# mcp23016-8buton8led_hw2_0.net
KiCad netlist of a schematic drawn in EAGLE
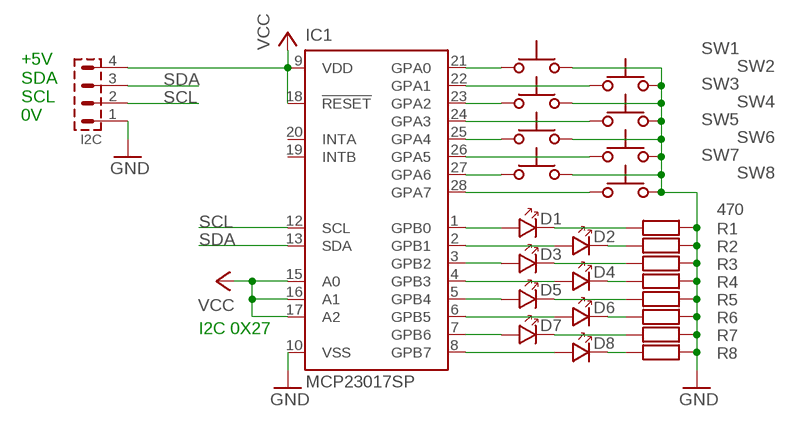
[diagram p0: schematic, sheet 1]

(export (version "E")
  (design (tool "Eeschema 10.0.6"))
  (components
    (comp (ref "D1")
      (value "LED_5")
      (footprint "eagle-import:LED_5")
      (libsource (lib "eagle-import") (part "LED_5"))
    )
    (comp (ref "D2")
      (value "LED_5")
      (footprint "eagle-import:LED_5")
      (libsource (lib "eagle-import") (part "LED_5"))
    )
    (comp (ref "D3")
      (value "LED_5")
      (footprint "eagle-import:LED_5")
      (libsource (lib "eagle-import") (part "LED_5"))
    )
    (comp (ref "D4")
      (value "LED_5")
      (footprint "eagle-import:LED_5")
      (libsource (lib "eagle-import") (part "LED_5"))
    )
    (comp (ref "D5")
      (value "LED_5")
      (footprint "eagle-import:LED_5")
      (libsource (lib "eagle-import") (part "LED_5"))
    )
    (comp (ref "D6")
      (value "LED_5")
      (footprint "eagle-import:LED_5")
      (libsource (lib "eagle-import") (part "LED_5"))
    )
    (comp (ref "D7")
      (value "LED_5")
      (footprint "eagle-import:LED_5")
      (libsource (lib "eagle-import") (part "LED_5"))
    )
    (comp (ref "D8")
      (value "LED_5")
      (footprint "eagle-import:LED_5")
      (libsource (lib "eagle-import") (part "LED_5"))
    )
    (comp (ref "I2C")
      (value "S1G4_JUMP")
      (footprint "eagle-import:S1G4_JUM")
      (libsource (lib "eagle-import") (part "S1G4_JUMP"))
    )
    (comp (ref "IC1")
      (value "MCP23017SP")
      (footprint "eagle-import:DIL28-3")
      (fields (field (name "MF") "MICROCHIP") (field (name "MPN") "MCP23017-E/SP"))
      (libsource (lib "eagle-import") (part "MCP23017SP"))
    )
    (comp (ref "R1")
      (value "470")
      (footprint "eagle-import:R-5")
      (libsource (lib "eagle-import") (part "R_5"))
    )
    (comp (ref "R2")
      (value "R_5")
      (footprint "eagle-import:R-5")
      (libsource (lib "eagle-import") (part "R_5"))
    )
    (comp (ref "R3")
      (value "R_5")
      (footprint "eagle-import:R-5")
      (libsource (lib "eagle-import") (part "R_5"))
    )
    (comp (ref "R4")
      (value "R_5")
      (footprint "eagle-import:R-5")
      (libsource (lib "eagle-import") (part "R_5"))
    )
    (comp (ref "R5")
      (value "R_5")
      (footprint "eagle-import:R-5")
      (libsource (lib "eagle-import") (part "R_5"))
    )
    (comp (ref "R6")
      (value "R_5")
      (footprint "eagle-import:R-5")
      (libsource (lib "eagle-import") (part "R_5"))
    )
    (comp (ref "R7")
      (value "R_5")
      (footprint "eagle-import:R-5")
      (libsource (lib "eagle-import") (part "R_5"))
    )
    (comp (ref "R8")
      (value "R_5")
      (footprint "eagle-import:R-5")
      (libsource (lib "eagle-import") (part "R_5"))
    )
    (comp (ref "SW1")
      (value "P-B1720")
      (footprint "eagle-import:P-B1720")
      (libsource (lib "eagle-import") (part "P-B1720"))
    )
    (comp (ref "SW2")
      (value "P-B1720")
      (footprint "eagle-import:P-B1720")
      (libsource (lib "eagle-import") (part "P-B1720"))
    )
    (comp (ref "SW3")
      (value "P-B1720")
      (footprint "eagle-import:P-B1720")
      (libsource (lib "eagle-import") (part "P-B1720"))
    )
    (comp (ref "SW4")
      (value "P-B1720")
      (footprint "eagle-import:P-B1720")
      (libsource (lib "eagle-import") (part "P-B1720"))
    )
    (comp (ref "SW5")
      (value "P-B1720")
      (footprint "eagle-import:P-B1720")
      (libsource (lib "eagle-import") (part "P-B1720"))
    )
    (comp (ref "SW6")
      (value "P-B1720")
      (footprint "eagle-import:P-B1720")
      (libsource (lib "eagle-import") (part "P-B1720"))
    )
    (comp (ref "SW7")
      (value "P-B1720")
      (footprint "eagle-import:P-B1720")
      (libsource (lib "eagle-import") (part "P-B1720"))
    )
    (comp (ref "SW8")
      (value "P-B1720")
      (footprint "eagle-import:P-B1720")
      (libsource (lib "eagle-import") (part "P-B1720"))
    )
  )
  (nets
    (net (code "1") (name "/SCL") (class "Default")
      (node (ref "I2C") (pin "2") (pinfunction "2_2") (pintype "passive"))
      (node (ref "IC1") (pin "12") (pinfunction "SCL_12") (pintype "input"))
    )
    (net (code "2") (name "/SDA") (class "Default")
      (node (ref "I2C") (pin "3") (pinfunction "3_3") (pintype "passive"))
      (node (ref "IC1") (pin "13") (pinfunction "SDA_13") (pintype "bidirectional"))
    )
    (net (code "3") (name "GND") (class "Default")
      (node (ref "I2C") (pin "1") (pinfunction "1_1") (pintype "passive"))
      (node (ref "IC1") (pin "10") (pinfunction "VSS_10") (pintype "power_in"))
      (node (ref "R1") (pin "2") (pinfunction "2_2") (pintype "passive"))
      (node (ref "R2") (pin "2") (pinfunction "2_2") (pintype "passive"))
      (node (ref "R3") (pin "2") (pinfunction "2_2") (pintype "passive"))
      (node (ref "R4") (pin "2") (pinfunction "2_2") (pintype "passive"))
      (node (ref "R5") (pin "2") (pinfunction "2_2") (pintype "passive"))
      (node (ref "R6") (pin "2") (pinfunction "2_2") (pintype "passive"))
      (node (ref "R7") (pin "2") (pinfunction "2_2") (pintype "passive"))
      (node (ref "R8") (pin "2") (pinfunction "2_2") (pintype "passive"))
      (node (ref "SW1") (pin "2") (pinfunction "2_2") (pintype "passive"))
      (node (ref "SW2") (pin "2") (pinfunction "2_2") (pintype "passive"))
      (node (ref "SW3") (pin "2") (pinfunction "2_2") (pintype "passive"))
      (node (ref "SW4") (pin "2") (pinfunction "2_2") (pintype "passive"))
      (node (ref "SW5") (pin "2") (pinfunction "2_2") (pintype "passive"))
      (node (ref "SW6") (pin "2") (pinfunction "2_2") (pintype "passive"))
      (node (ref "SW7") (pin "2") (pinfunction "2_2") (pintype "passive"))
      (node (ref "SW8") (pin "2") (pinfunction "2_2") (pintype "passive"))
    )
    (net (code "4") (name "Net-(D1-PadK)") (class "Default")
      (node (ref "D1") (pin "K") (pinfunction "K_K") (pintype "passive"))
      (node (ref "R1") (pin "1") (pinfunction "1_1") (pintype "passive"))
    )
    (net (code "5") (name "Net-(D2-PadK)") (class "Default")
      (node (ref "D2") (pin "K") (pinfunction "K_K") (pintype "passive"))
      (node (ref "R2") (pin "1") (pinfunction "1_1") (pintype "passive"))
    )
    (net (code "6") (name "Net-(D3-PadK)") (class "Default")
      (node (ref "D3") (pin "K") (pinfunction "K_K") (pintype "passive"))
      (node (ref "R3") (pin "1") (pinfunction "1_1") (pintype "passive"))
    )
    (net (code "7") (name "Net-(D4-PadK)") (class "Default")
      (node (ref "D4") (pin "K") (pinfunction "K_K") (pintype "passive"))
      (node (ref "R4") (pin "1") (pinfunction "1_1") (pintype "passive"))
    )
    (net (code "8") (name "Net-(D5-PadK)") (class "Default")
      (node (ref "D5") (pin "K") (pinfunction "K_K") (pintype "passive"))
      (node (ref "R5") (pin "1") (pinfunction "1_1") (pintype "passive"))
    )
    (net (code "9") (name "Net-(D6-PadK)") (class "Default")
      (node (ref "D6") (pin "K") (pinfunction "K_K") (pintype "passive"))
      (node (ref "R6") (pin "1") (pinfunction "1_1") (pintype "passive"))
    )
    (net (code "10") (name "Net-(D7-PadK)") (class "Default")
      (node (ref "D7") (pin "K") (pinfunction "K_K") (pintype "passive"))
      (node (ref "R7") (pin "1") (pinfunction "1_1") (pintype "passive"))
    )
    (net (code "11") (name "Net-(D8-PadK)") (class "Default")
      (node (ref "D8") (pin "K") (pinfunction "K_K") (pintype "passive"))
      (node (ref "R8") (pin "1") (pinfunction "1_1") (pintype "passive"))
    )
    (net (code "12") (name "Net-(IC1-GPA0)") (class "Default")
      (node (ref "IC1") (pin "21") (pinfunction "GPA0_21") (pintype "bidirectional"))
      (node (ref "SW1") (pin "1") (pinfunction "1_1") (pintype "passive"))
    )
    (net (code "13") (name "Net-(IC1-GPA1)") (class "Default")
      (node (ref "IC1") (pin "22") (pinfunction "GPA1_22") (pintype "bidirectional"))
      (node (ref "SW2") (pin "1") (pinfunction "1_1") (pintype "passive"))
    )
    (net (code "14") (name "Net-(IC1-GPA2)") (class "Default")
      (node (ref "IC1") (pin "23") (pinfunction "GPA2_23") (pintype "bidirectional"))
      (node (ref "SW3") (pin "1") (pinfunction "1_1") (pintype "passive"))
    )
    (net (code "15") (name "Net-(IC1-GPA3)") (class "Default")
      (node (ref "IC1") (pin "24") (pinfunction "GPA3_24") (pintype "bidirectional"))
      (node (ref "SW4") (pin "1") (pinfunction "1_1") (pintype "passive"))
    )
    (net (code "16") (name "Net-(IC1-GPA4)") (class "Default")
      (node (ref "IC1") (pin "25") (pinfunction "GPA4_25") (pintype "bidirectional"))
      (node (ref "SW5") (pin "1") (pinfunction "1_1") (pintype "passive"))
    )
    (net (code "17") (name "Net-(IC1-GPA5)") (class "Default")
      (node (ref "IC1") (pin "26") (pinfunction "GPA5_26") (pintype "bidirectional"))
      (node (ref "SW6") (pin "1") (pinfunction "1_1") (pintype "passive"))
    )
    (net (code "18") (name "Net-(IC1-GPA6)") (class "Default")
      (node (ref "IC1") (pin "27") (pinfunction "GPA6_27") (pintype "bidirectional"))
      (node (ref "SW7") (pin "1") (pinfunction "1_1") (pintype "passive"))
    )
    (net (code "19") (name "Net-(IC1-GPA7)") (class "Default")
      (node (ref "IC1") (pin "28") (pinfunction "GPA7_28") (pintype "bidirectional"))
      (node (ref "SW8") (pin "1") (pinfunction "1_1") (pintype "passive"))
    )
    (net (code "20") (name "Net-(IC1-GPB0)") (class "Default")
      (node (ref "D1") (pin "A") (pinfunction "A_A") (pintype "passive"))
      (node (ref "IC1") (pin "1") (pinfunction "GPB0_1") (pintype "bidirectional"))
    )
    (net (code "21") (name "Net-(IC1-GPB1)") (class "Default")
      (node (ref "D2") (pin "A") (pinfunction "A_A") (pintype "passive"))
      (node (ref "IC1") (pin "2") (pinfunction "GPB1_2") (pintype "bidirectional"))
    )
    (net (code "22") (name "Net-(IC1-GPB2)") (class "Default")
      (node (ref "D3") (pin "A") (pinfunction "A_A") (pintype "passive"))
      (node (ref "IC1") (pin "3") (pinfunction "GPB2_3") (pintype "bidirectional"))
    )
    (net (code "23") (name "Net-(IC1-GPB3)") (class "Default")
      (node (ref "D4") (pin "A") (pinfunction "A_A") (pintype "passive"))
      (node (ref "IC1") (pin "4") (pinfunction "GPB3_4") (pintype "bidirectional"))
    )
    (net (code "24") (name "Net-(IC1-GPB4)") (class "Default")
      (node (ref "D5") (pin "A") (pinfunction "A_A") (pintype "passive"))
      (node (ref "IC1") (pin "5") (pinfunction "GPB4_5") (pintype "bidirectional"))
    )
    (net (code "25") (name "Net-(IC1-GPB5)") (class "Default")
      (node (ref "D6") (pin "A") (pinfunction "A_A") (pintype "passive"))
      (node (ref "IC1") (pin "6") (pinfunction "GPB5_6") (pintype "bidirectional"))
    )
    (net (code "26") (name "Net-(IC1-GPB6)") (class "Default")
      (node (ref "D7") (pin "A") (pinfunction "A_A") (pintype "passive"))
      (node (ref "IC1") (pin "7") (pinfunction "GPB6_7") (pintype "bidirectional"))
    )
    (net (code "27") (name "Net-(IC1-GPB7)") (class "Default")
      (node (ref "D8") (pin "A") (pinfunction "A_A") (pintype "passive"))
      (node (ref "IC1") (pin "8") (pinfunction "GPB7_8") (pintype "bidirectional"))
    )
    (net (code "28") (name "VCC") (class "Default")
      (node (ref "I2C") (pin "4") (pinfunction "4_4") (pintype "passive"))
      (node (ref "IC1") (pin "15") (pinfunction "A0_15") (pintype "input"))
      (node (ref "IC1") (pin "16") (pinfunction "A1_16") (pintype "input"))
      (node (ref "IC1") (pin "17") (pinfunction "A2_17") (pintype "input"))
      (node (ref "IC1") (pin "18") (pinfunction "~{RESET}_18") (pintype "input"))
      (node (ref "IC1") (pin "9") (pinfunction "VDD_9") (pintype "power_in"))
    )
    (net (code "29") (name "unconnected-(IC1-INTA-Pad20)") (class "Default")
      (node (ref "IC1") (pin "20") (pinfunction "INTA_20") (pintype "output"))
    )
    (net (code "30") (name "unconnected-(IC1-INTB-Pad19)") (class "Default")
      (node (ref "IC1") (pin "19") (pinfunction "INTB_19") (pintype "output"))
    )
    (net (code "31") (name "unconnected-(SW1-1A-Pad3)") (class "Default")
      (node (ref "SW1") (pin "3") (pinfunction "1A_3") (pintype "passive"))
    )
    (net (code "32") (name "unconnected-(SW1-2A-Pad4)") (class "Default")
      (node (ref "SW1") (pin "4") (pinfunction "2A_4") (pintype "passive"))
    )
    (net (code "33") (name "unconnected-(SW2-1A-Pad3)") (class "Default")
      (node (ref "SW2") (pin "3") (pinfunction "1A_3") (pintype "passive"))
    )
    (net (code "34") (name "unconnected-(SW2-2A-Pad4)") (class "Default")
      (node (ref "SW2") (pin "4") (pinfunction "2A_4") (pintype "passive"))
    )
    (net (code "35") (name "unconnected-(SW3-1A-Pad3)") (class "Default")
      (node (ref "SW3") (pin "3") (pinfunction "1A_3") (pintype "passive"))
    )
    (net (code "36") (name "unconnected-(SW3-2A-Pad4)") (class "Default")
      (node (ref "SW3") (pin "4") (pinfunction "2A_4") (pintype "passive"))
    )
    (net (code "37") (name "unconnected-(SW4-1A-Pad3)") (class "Default")
      (node (ref "SW4") (pin "3") (pinfunction "1A_3") (pintype "passive"))
    )
    (net (code "38") (name "unconnected-(SW4-2A-Pad4)") (class "Default")
      (node (ref "SW4") (pin "4") (pinfunction "2A_4") (pintype "passive"))
    )
    (net (code "39") (name "unconnected-(SW5-1A-Pad3)") (class "Default")
      (node (ref "SW5") (pin "3") (pinfunction "1A_3") (pintype "passive"))
    )
    (net (code "40") (name "unconnected-(SW5-2A-Pad4)") (class "Default")
      (node (ref "SW5") (pin "4") (pinfunction "2A_4") (pintype "passive"))
    )
    (net (code "41") (name "unconnected-(SW6-1A-Pad3)") (class "Default")
      (node (ref "SW6") (pin "3") (pinfunction "1A_3") (pintype "passive"))
    )
    (net (code "42") (name "unconnected-(SW6-2A-Pad4)") (class "Default")
      (node (ref "SW6") (pin "4") (pinfunction "2A_4") (pintype "passive"))
    )
    (net (code "43") (name "unconnected-(SW7-1A-Pad3)") (class "Default")
      (node (ref "SW7") (pin "3") (pinfunction "1A_3") (pintype "passive"))
    )
    (net (code "44") (name "unconnected-(SW7-2A-Pad4)") (class "Default")
      (node (ref "SW7") (pin "4") (pinfunction "2A_4") (pintype "passive"))
    )
    (net (code "45") (name "unconnected-(SW8-1A-Pad3)") (class "Default")
      (node (ref "SW8") (pin "3") (pinfunction "1A_3") (pintype "passive"))
    )
    (net (code "46") (name "unconnected-(SW8-2A-Pad4)") (class "Default")
      (node (ref "SW8") (pin "4") (pinfunction "2A_4") (pintype "passive"))
    )
  )
)
